# Power.net
KiCad netlist of a schematic drawn in Altium Designer
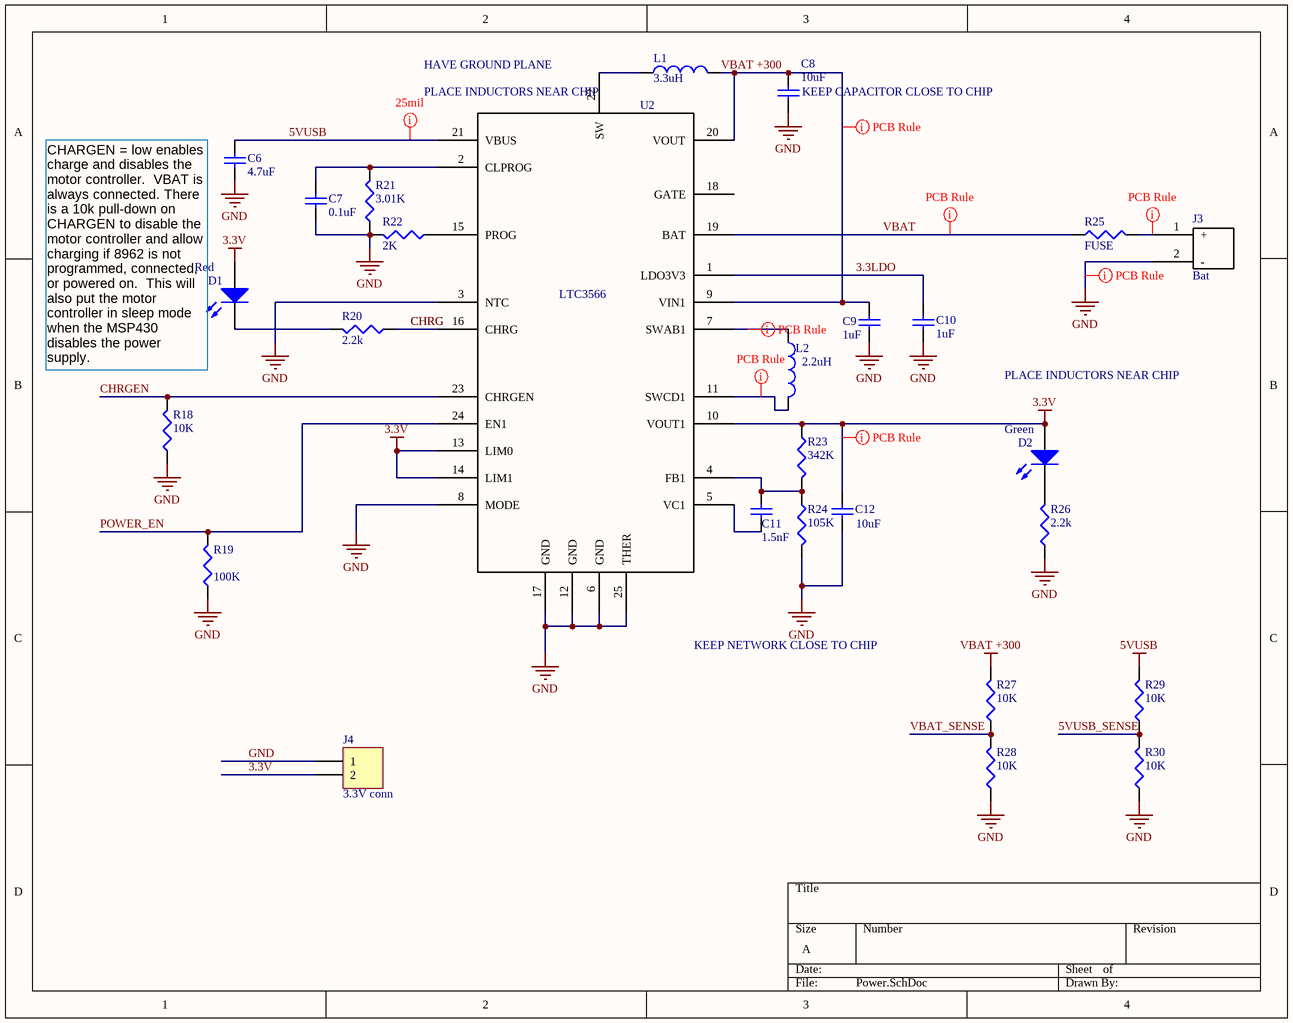
[diagram p0: Power.SchDoc]

(export (version "E")
  (design (tool "Eeschema 10.0.6"))
  (components
    (comp (ref "C6")
      (value "4.7uF")
      (footprint "CAPC1608L")
      (description "Capacitor")
      (fields (field (name "Comment") "Cap") (field (name "PUBLISHER") "Altium Limited"))
      (libsource (lib "Miscellaneous Devices") (part "Cap"))
    )
    (comp (ref "C7")
      (value "0.1uF")
      (footprint "CAPC1005L")
      (description "Capacitor")
      (fields (field (name "Comment") "Cap") (field (name "PUBLISHER") "Altium Limited"))
      (libsource (lib "Miscellaneous Devices") (part "Cap"))
    )
    (comp (ref "C8")
      (value "10uF")
      (footprint "CAPC1608L")
      (description "Capacitor")
      (fields (field (name "Comment") "Cap") (field (name "PUBLISHER") "Altium Limited"))
      (libsource (lib "Miscellaneous Devices") (part "Cap"))
    )
    (comp (ref "C9")
      (value "1uF")
      (footprint "CAPC1608L")
      (description "Capacitor")
      (fields (field (name "Comment") "Cap") (field (name "PUBLISHER") "Altium Limited"))
      (libsource (lib "Miscellaneous Devices") (part "Cap"))
    )
    (comp (ref "C10")
      (value "1uF")
      (footprint "CAPC1608L")
      (description "Capacitor")
      (fields (field (name "Comment") "Cap") (field (name "PUBLISHER") "Altium Limited"))
      (libsource (lib "Miscellaneous Devices") (part "Cap"))
    )
    (comp (ref "C11")
      (value "1.5nF")
      (footprint "CAPC1005L")
      (description "Capacitor")
      (fields (field (name "Comment") "Cap") (field (name "PUBLISHER") "Altium Limited"))
      (libsource (lib "Miscellaneous Devices") (part "Cap"))
    )
    (comp (ref "C12")
      (value "10uF")
      (footprint "CAPC1608L")
      (description "Capacitor")
      (fields (field (name "Comment") "Cap") (field (name "PUBLISHER") "Altium Limited"))
      (libsource (lib "Miscellaneous Devices") (part "Cap"))
    )
    (comp (ref "D1")
      (value "Red")
      (footprint "INDC2012L")
      (description "Typical RED, GREEN, YELLOW, AMBER GaAs LED")
      (fields (field (name "PUBLISHER") "Altium Limited"))
      (libsource (lib "Miscellaneous Devices") (part "LED2"))
    )
    (comp (ref "D2")
      (value "Green")
      (footprint "INDC2012L")
      (description "Typical RED, GREEN, YELLOW, AMBER GaAs LED")
      (fields (field (name "PUBLISHER") "Altium Limited"))
      (libsource (lib "Miscellaneous Devices") (part "LED2"))
    )
    (comp (ref "J3")
      (value "Bat")
      (footprint "BatteryConnJST")
      (libsource (lib "mrone") (part "BatteryConnJST"))
    )
    (comp (ref "J4")
      (value "3.3V conn")
      (footprint "HDR1X2")
      (description "Header, 2-Pin")
      (fields (field (name "PUBLISHER") "Altium Limited"))
      (libsource (lib "Miscellaneous Connectors") (part "Header 2"))
    )
    (comp (ref "L1") (value "3.3uH") (footprint "IndPow") (libsource (lib "mrone") (part "Inductor")))
    (comp (ref "L2") (value "2.2uH") (footprint "IndPow") (libsource (lib "mrone") (part "Inductor")))
    (comp (ref "R18")
      (value "10K")
      (footprint "RESC1608L")
      (description "Resistor")
      (fields (field (name "Comment") "Res3") (field (name "PUBLISHER") "Altium Limited"))
      (libsource (lib "Miscellaneous Devices") (part "Res3"))
    )
    (comp (ref "R19")
      (value "100K")
      (footprint "RESC1608L")
      (description "Resistor")
      (fields (field (name "Comment") "Res3") (field (name "PUBLISHER") "Altium Limited"))
      (libsource (lib "Miscellaneous Devices") (part "Res3"))
    )
    (comp (ref "R20")
      (value "2.2k")
      (footprint "RESC1608L")
      (description "Resistor")
      (fields (field (name "Comment") "Res3") (field (name "PUBLISHER") "Altium Limited"))
      (libsource (lib "Miscellaneous Devices") (part "Res3"))
    )
    (comp (ref "R21")
      (value "3.01K")
      (footprint "RESC1608L")
      (description "Resistor")
      (fields (field (name "Comment") "Res3") (field (name "PUBLISHER") "Altium Limited"))
      (libsource (lib "Miscellaneous Devices") (part "Res3"))
    )
    (comp (ref "R22")
      (value "2K")
      (footprint "RESC1608L")
      (description "Resistor")
      (fields (field (name "Comment") "Res3") (field (name "PUBLISHER") "Altium Limited"))
      (libsource (lib "Miscellaneous Devices") (part "Res3"))
    )
    (comp (ref "R23")
      (value "342K")
      (footprint "RESC1608L")
      (description "Resistor")
      (fields (field (name "Comment") "Res3") (field (name "PUBLISHER") "Altium Limited"))
      (libsource (lib "Miscellaneous Devices") (part "Res3"))
    )
    (comp (ref "R24")
      (value "105K")
      (footprint "RESC1608L")
      (description "Resistor")
      (fields (field (name "Comment") "Res3") (field (name "PUBLISHER") "Altium Limited"))
      (libsource (lib "Miscellaneous Devices") (part "Res3"))
    )
    (comp (ref "R25")
      (value "FUSE")
      (footprint "RESC3225L")
      (description "Resistor")
      (fields (field (name "Comment") "Res3") (field (name "PUBLISHER") "Altium Limited"))
      (libsource (lib "Miscellaneous Devices") (part "Res3"))
    )
    (comp (ref "R26")
      (value "2.2k")
      (footprint "RESC1608L")
      (description "Resistor")
      (fields (field (name "Comment") "Res3") (field (name "PUBLISHER") "Altium Limited"))
      (libsource (lib "Miscellaneous Devices") (part "Res3"))
    )
    (comp (ref "R27")
      (value "10K")
      (footprint "RESC1608L")
      (description "Resistor")
      (fields (field (name "Comment") "Res3") (field (name "PUBLISHER") "Altium Limited"))
      (libsource (lib "Miscellaneous Devices") (part "Res3"))
    )
    (comp (ref "R28")
      (value "10K")
      (footprint "RESC1608L")
      (description "Resistor")
      (fields (field (name "Comment") "Res3") (field (name "PUBLISHER") "Altium Limited"))
      (libsource (lib "Miscellaneous Devices") (part "Res3"))
    )
    (comp (ref "R29")
      (value "10K")
      (footprint "RESC1608L")
      (description "Resistor")
      (fields (field (name "Comment") "Res3") (field (name "PUBLISHER") "Altium Limited"))
      (libsource (lib "Miscellaneous Devices") (part "Res3"))
    )
    (comp (ref "R30")
      (value "10K")
      (footprint "RESC1608L")
      (description "Resistor")
      (fields (field (name "Comment") "Res3") (field (name "PUBLISHER") "Altium Limited"))
      (libsource (lib "Miscellaneous Devices") (part "Res3"))
    )
    (comp (ref "U2")
      (value "LTC3566")
      (footprint "QFN-24")
      (libsource (lib "Schematic Components") (part "LTC3566"))
    )
  )
  (nets
    (net (code "1") (name "/3.3LDO") (class "Default")
      (node (ref "C10") (pin "1") (pinfunction "1_1") (pintype "passive"))
      (node (ref "U2") (pin "1") (pinfunction "LDO3V3_1") (pintype "passive"))
    )
    (net (code "2") (name "/5VUSB_SENSE") (class "Default")
      (node (ref "R29") (pin "1") (pinfunction "1_1") (pintype "passive"))
      (node (ref "R30") (pin "2") (pinfunction "2_2") (pintype "passive"))
    )
    (net (code "3") (name "/CHRG") (class "Default")
      (node (ref "R20") (pin "1") (pinfunction "1_1") (pintype "passive"))
      (node (ref "U2") (pin "16") (pinfunction "CHRG_16") (pintype "passive"))
    )
    (net (code "4") (name "/CHRGEN") (class "Default")
      (node (ref "R18") (pin "2") (pinfunction "2_2") (pintype "passive"))
      (node (ref "U2") (pin "23") (pinfunction "CHRGEN_23") (pintype "passive"))
    )
    (net (code "5") (name "/POWER_EN") (class "Default")
      (node (ref "R19") (pin "2") (pinfunction "2_2") (pintype "passive"))
      (node (ref "U2") (pin "24") (pinfunction "EN1_24") (pintype "passive"))
    )
    (net (code "6") (name "/VBAT") (class "Default")
      (node (ref "R25") (pin "1") (pinfunction "1_1") (pintype "passive"))
      (node (ref "U2") (pin "19") (pinfunction "BAT_19") (pintype "passive"))
    )
    (net (code "7") (name "/VBAT_SENSE") (class "Default")
      (node (ref "R27") (pin "1") (pinfunction "1_1") (pintype "passive"))
      (node (ref "R28") (pin "2") (pinfunction "2_2") (pintype "passive"))
    )
    (net (code "8") (name "3.3V") (class "Default")
      (node (ref "C12") (pin "2") (pinfunction "2_2") (pintype "passive"))
      (node (ref "D1") (pin "1") (pinfunction "A_1") (pintype "passive"))
      (node (ref "D2") (pin "1") (pinfunction "A_1") (pintype "passive"))
      (node (ref "J4") (pin "2") (pinfunction "2_2") (pintype "passive"))
      (node (ref "R23") (pin "1") (pinfunction "1_1") (pintype "passive"))
      (node (ref "U2") (pin "10") (pinfunction "VOUT1_10") (pintype "passive"))
      (node (ref "U2") (pin "13") (pinfunction "LIM0_13") (pintype "passive"))
      (node (ref "U2") (pin "14") (pinfunction "LIM1_14") (pintype "passive"))
    )
    (net (code "9") (name "5VUSB") (class "Default")
      (node (ref "C6") (pin "2") (pinfunction "2_2") (pintype "passive"))
      (node (ref "R29") (pin "2") (pinfunction "2_2") (pintype "passive"))
      (node (ref "U2") (pin "21") (pinfunction "VBUS_21") (pintype "passive"))
    )
    (net (code "10") (name "GND") (class "Default")
      (node (ref "C10") (pin "2") (pinfunction "2_2") (pintype "passive"))
      (node (ref "C12") (pin "1") (pinfunction "1_1") (pintype "passive"))
      (node (ref "C6") (pin "1") (pinfunction "1_1") (pintype "passive"))
      (node (ref "C7") (pin "1") (pinfunction "1_1") (pintype "passive"))
      (node (ref "C8") (pin "1") (pinfunction "1_1") (pintype "passive"))
      (node (ref "C9") (pin "2") (pinfunction "2_2") (pintype "passive"))
      (node (ref "J3") (pin "2") (pinfunction "-_2") (pintype "passive"))
      (node (ref "J4") (pin "1") (pinfunction "1_1") (pintype "passive"))
      (node (ref "R18") (pin "1") (pinfunction "1_1") (pintype "passive"))
      (node (ref "R19") (pin "1") (pinfunction "1_1") (pintype "passive"))
      (node (ref "R21") (pin "1") (pinfunction "1_1") (pintype "passive"))
      (node (ref "R22") (pin "2") (pinfunction "2_2") (pintype "passive"))
      (node (ref "R24") (pin "2") (pinfunction "2_2") (pintype "passive"))
      (node (ref "R26") (pin "1") (pinfunction "1_1") (pintype "passive"))
      (node (ref "R28") (pin "1") (pinfunction "1_1") (pintype "passive"))
      (node (ref "R30") (pin "1") (pinfunction "1_1") (pintype "passive"))
      (node (ref "U2") (pin "12") (pinfunction "GND_12") (pintype "passive"))
      (node (ref "U2") (pin "17") (pinfunction "GND_17") (pintype "passive"))
      (node (ref "U2") (pin "25") (pinfunction "THER_25") (pintype "passive"))
      (node (ref "U2") (pin "3") (pinfunction "NTC_3") (pintype "passive"))
      (node (ref "U2") (pin "6") (pinfunction "GND_6") (pintype "passive"))
      (node (ref "U2") (pin "8") (pinfunction "MODE_8") (pintype "passive"))
    )
    (net (code "11") (name "Net-(D1-K)") (class "Default")
      (node (ref "D1") (pin "2") (pinfunction "K_2") (pintype "passive"))
      (node (ref "R20") (pin "2") (pinfunction "2_2") (pintype "passive"))
    )
    (net (code "12") (name "Net-(D2-K)") (class "Default")
      (node (ref "D2") (pin "2") (pinfunction "K_2") (pintype "passive"))
      (node (ref "R26") (pin "2") (pinfunction "2_2") (pintype "passive"))
    )
    (net (code "13") (name "Net-(J3-+)") (class "Default")
      (node (ref "J3") (pin "1") (pinfunction "+_1") (pintype "passive"))
      (node (ref "R25") (pin "2") (pinfunction "2_2") (pintype "passive"))
    )
    (net (code "14") (name "Net-(U2-CLPROG)") (class "Default")
      (node (ref "C7") (pin "2") (pinfunction "2_2") (pintype "passive"))
      (node (ref "R21") (pin "2") (pinfunction "2_2") (pintype "passive"))
      (node (ref "U2") (pin "2") (pinfunction "CLPROG_2") (pintype "passive"))
    )
    (net (code "15") (name "Net-(U2-FB1)") (class "Default")
      (node (ref "C11") (pin "1") (pinfunction "1_1") (pintype "passive"))
      (node (ref "R23") (pin "2") (pinfunction "2_2") (pintype "passive"))
      (node (ref "R24") (pin "1") (pinfunction "1_1") (pintype "passive"))
      (node (ref "U2") (pin "4") (pinfunction "FB1_4") (pintype "passive"))
    )
    (net (code "16") (name "Net-(U2-PROG)") (class "Default")
      (node (ref "R22") (pin "1") (pinfunction "1_1") (pintype "passive"))
      (node (ref "U2") (pin "15") (pinfunction "PROG_15") (pintype "passive"))
    )
    (net (code "17") (name "Net-(U2-SW)") (class "Default")
      (node (ref "L1") (pin "1") (pinfunction "1_1") (pintype "passive"))
      (node (ref "U2") (pin "22") (pinfunction "SW_22") (pintype "passive"))
    )
    (net (code "18") (name "Net-(U2-SWAB1)") (class "Default")
      (node (ref "L2") (pin "1") (pinfunction "1_1") (pintype "passive"))
      (node (ref "U2") (pin "7") (pinfunction "SWAB1_7") (pintype "passive"))
    )
    (net (code "19") (name "Net-(U2-SWCD1)") (class "Default")
      (node (ref "L2") (pin "2") (pinfunction "2_2") (pintype "passive"))
      (node (ref "U2") (pin "11") (pinfunction "SWCD1_11") (pintype "passive"))
    )
    (net (code "20") (name "Net-(U2-VC1)") (class "Default")
      (node (ref "C11") (pin "2") (pinfunction "2_2") (pintype "passive"))
      (node (ref "U2") (pin "5") (pinfunction "VC1_5") (pintype "passive"))
    )
    (net (code "21") (name "VBAT +300") (class "Default")
      (node (ref "C8") (pin "2") (pinfunction "2_2") (pintype "passive"))
      (node (ref "C9") (pin "1") (pinfunction "1_1") (pintype "passive"))
      (node (ref "L1") (pin "2") (pinfunction "2_2") (pintype "passive"))
      (node (ref "R27") (pin "2") (pinfunction "2_2") (pintype "passive"))
      (node (ref "U2") (pin "20") (pinfunction "VOUT_20") (pintype "passive"))
      (node (ref "U2") (pin "9") (pinfunction "VIN1_9") (pintype "passive"))
    )
    (net (code "22") (name "unconnected-(U2-GATE-Pad18)") (class "Default")
      (node (ref "U2") (pin "18") (pinfunction "GATE_18") (pintype "passive"))
    )
  )
)
